# PowerV2.net
KiCad netlist of a schematic drawn in Altium Designer
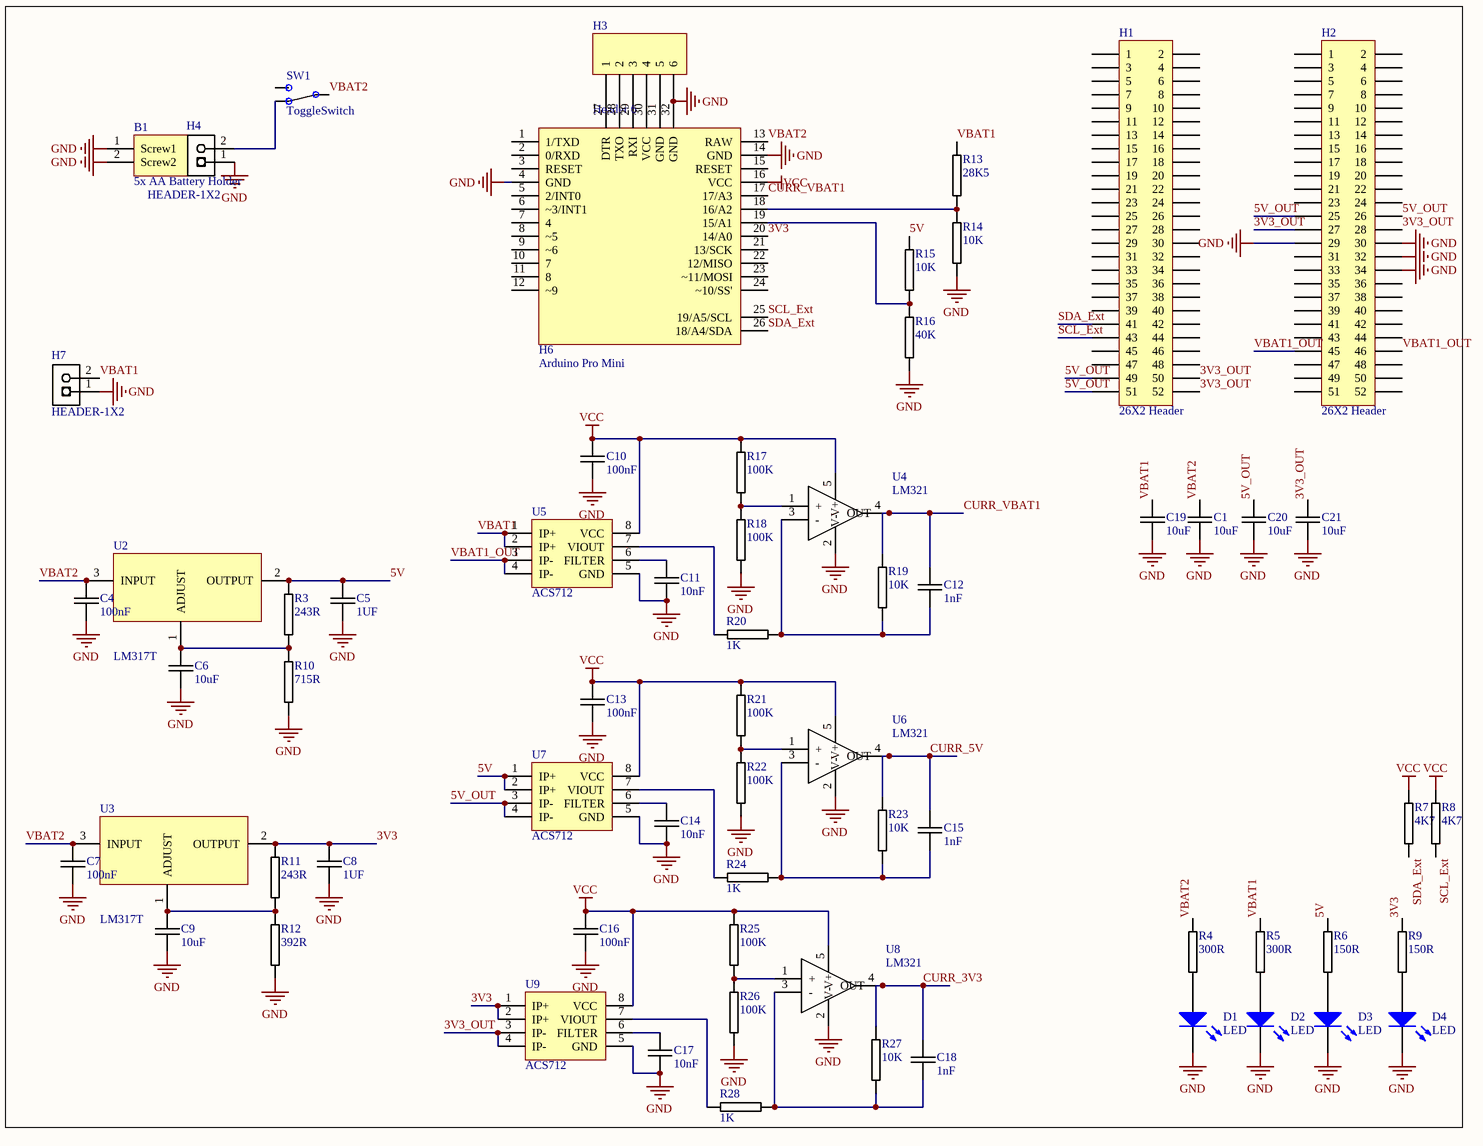
[diagram p0: PowerV2.SchDoc]

(export (version "E")
  (design (tool "Eeschema 10.0.6"))
  (components
    (comp (ref "B1")
      (value "5x AA Battery Holder")
      (footprint "5x AA Battery Holder")
      (libsource (lib "SupportComponents") (part "5x AA Battery Holder"))
    )
    (comp (ref "C1")
      (value "10uF")
      (footprint "0805C-GENERIC")
      (description "CAPACITOR 0805 CERAMIC")
      (fields
        (field (name "MANUFACTURER PART NUMBER") "C2012X5R1C106M")
        (field (name "MANUFACTURER") "TDK Corporation")
      )
      (libsource (lib "vh_altium_library") (part "0805C-10UF-16V-X5R-TDK"))
    )
    (comp (ref "C4")
      (value "100nF")
      (footprint "0805C-TBD")
      (description "CAPACITOR 0805 CERAMIC")
      (libsource (lib "vh_altium_library") (part "0805C-100nF-25V-X7R-MUR"))
    )
    (comp (ref "C5")
      (value "1UF")
      (footprint "0805C-GENERIC")
      (description "CAPACITOR 0805 CERAMIC")
      (fields
        (field (name "MANUFACTURER PART NUMBER") "ECJ-1VB0J225K")
        (field (name "MANUFACTURER") "Panasonic - ECG")
      )
      (libsource (lib "vh_altium_library") (part "0805C-2U2-6V3-X5R-PAN"))
    )
    (comp (ref "C6")
      (value "10uF")
      (footprint "0805C-GENERIC")
      (description "CAPACITOR 0805 CERAMIC")
      (libsource (lib "vh_altium_library") (part "0805C-10UF-25V-X5R-SAM"))
    )
    (comp (ref "C7")
      (value "100nF")
      (footprint "0805C-TBD")
      (description "CAPACITOR 0805 CERAMIC")
      (libsource (lib "vh_altium_library") (part "0805C-100nF-25V-X7R-MUR"))
    )
    (comp (ref "C8")
      (value "1UF")
      (footprint "0805C-GENERIC")
      (description "CAPACITOR 0805 CERAMIC")
      (fields
        (field (name "MANUFACTURER PART NUMBER") "ECJ-1VB0J225K")
        (field (name "MANUFACTURER") "Panasonic - ECG")
      )
      (libsource (lib "vh_altium_library") (part "0805C-2U2-6V3-X5R-PAN"))
    )
    (comp (ref "C9")
      (value "10uF")
      (footprint "0805C-GENERIC")
      (description "CAPACITOR 0805 CERAMIC")
      (libsource (lib "vh_altium_library") (part "0805C-10UF-25V-X5R-SAM"))
    )
    (comp (ref "C10")
      (value "100nF")
      (footprint "0805C-TBD")
      (description "CAPACITOR 0805 CERAMIC")
      (libsource (lib "vh_altium_library") (part "0805C-100nF-25V-X7R-MUR"))
    )
    (comp (ref "C11")
      (value "10nF")
      (footprint "0805C-TBD")
      (description "CAPACITOR 0805 CERAMIC")
      (libsource (lib "vh_altium_library") (part "0805C-100nF-25V-X7R-MUR"))
    )
    (comp (ref "C12")
      (value "1nF")
      (footprint "0805C-TBD")
      (description "CAPACITOR 0805 CERAMIC")
      (libsource (lib "vh_altium_library") (part "0805C-100nF-25V-X7R-MUR"))
    )
    (comp (ref "C13")
      (value "100nF")
      (footprint "0805C-TBD")
      (description "CAPACITOR 0805 CERAMIC")
      (libsource (lib "vh_altium_library") (part "0805C-100nF-25V-X7R-MUR"))
    )
    (comp (ref "C14")
      (value "10nF")
      (footprint "0805C-TBD")
      (description "CAPACITOR 0805 CERAMIC")
      (libsource (lib "vh_altium_library") (part "0805C-100nF-25V-X7R-MUR"))
    )
    (comp (ref "C15")
      (value "1nF")
      (footprint "0805C-TBD")
      (description "CAPACITOR 0805 CERAMIC")
      (libsource (lib "vh_altium_library") (part "0805C-100nF-25V-X7R-MUR"))
    )
    (comp (ref "C16")
      (value "100nF")
      (footprint "0805C-TBD")
      (description "CAPACITOR 0805 CERAMIC")
      (libsource (lib "vh_altium_library") (part "0805C-100nF-25V-X7R-MUR"))
    )
    (comp (ref "C17")
      (value "10nF")
      (footprint "0805C-TBD")
      (description "CAPACITOR 0805 CERAMIC")
      (libsource (lib "vh_altium_library") (part "0805C-100nF-25V-X7R-MUR"))
    )
    (comp (ref "C18")
      (value "1nF")
      (footprint "0805C-TBD")
      (description "CAPACITOR 0805 CERAMIC")
      (libsource (lib "vh_altium_library") (part "0805C-100nF-25V-X7R-MUR"))
    )
    (comp (ref "C19")
      (value "10uF")
      (footprint "0805C-GENERIC")
      (description "CAPACITOR 0805 CERAMIC")
      (fields
        (field (name "MANUFACTURER PART NUMBER") "C2012X5R1C106M")
        (field (name "MANUFACTURER") "TDK Corporation")
      )
      (libsource (lib "vh_altium_library") (part "0805C-10UF-16V-X5R-TDK"))
    )
    (comp (ref "C20")
      (value "10uF")
      (footprint "0805C-GENERIC")
      (description "CAPACITOR 0805 CERAMIC")
      (fields
        (field (name "MANUFACTURER PART NUMBER") "C2012X5R1C106M")
        (field (name "MANUFACTURER") "TDK Corporation")
      )
      (libsource (lib "vh_altium_library") (part "0805C-10UF-16V-X5R-TDK"))
    )
    (comp (ref "C21")
      (value "10uF")
      (footprint "0805C-GENERIC")
      (description "CAPACITOR 0805 CERAMIC")
      (fields
        (field (name "MANUFACTURER PART NUMBER") "C2012X5R1C106M")
        (field (name "MANUFACTURER") "TDK Corporation")
      )
      (libsource (lib "vh_altium_library") (part "0805C-10UF-16V-X5R-TDK"))
    )
    (comp (ref "D1")
      (value "LED")
      (footprint "LED")
      (description "Small LED")
      (libsource (lib "SupportComponents") (part "LED"))
    )
    (comp (ref "D2")
      (value "LED")
      (footprint "LED")
      (description "Small LED")
      (libsource (lib "SupportComponents") (part "LED"))
    )
    (comp (ref "D3")
      (value "LED")
      (footprint "LED")
      (description "Small LED")
      (libsource (lib "SupportComponents") (part "LED"))
    )
    (comp (ref "D4")
      (value "LED")
      (footprint "LED")
      (description "Small LED")
      (libsource (lib "SupportComponents") (part "LED"))
    )
    (comp (ref "H1")
      (value "26X2 Header")
      (footprint "26X2 Header")
      (libsource (lib "CustomParts") (part "26X2 Header"))
    )
    (comp (ref "H2")
      (value "26X2 Header")
      (footprint "26X2 Header")
      (libsource (lib "CustomParts") (part "26X2 Header"))
    )
    (comp (ref "H3")
      (value "Header 6")
      (footprint "HDR1X6")
      (description "Header, 6-Pin")
      (fields (field (name "PUBLISHER") "Altium Limited"))
      (libsource (lib "Miscellaneous Connectors") (part "Header 6"))
    )
    (comp (ref "H4")
      (value "HEADER-1X2")
      (footprint "HEADER-1X2")
      (libsource (lib "vh_altium_library") (part "HEADER-1X2"))
    )
    (comp (ref "H6")
      (value "Arduino Pro Mini")
      (footprint "Arduino Pro Mini")
      (libsource (lib "SupportComponents") (part "Arduino Pro Mini"))
    )
    (comp (ref "H7")
      (value "HEADER-1X2")
      (footprint "HEADER-1X2")
      (libsource (lib "vh_altium_library") (part "HEADER-1X2"))
    )
    (comp (ref "R3")
      (value "243R")
      (footprint "0805R-GENERIC")
      (description "RESISTOR 0805 1/3 WATT")
      (libsource (lib "vh_altium_library") (part "0805R-1R"))
    )
    (comp (ref "R4")
      (value "300R")
      (footprint "0805R-150")
      (description "RESISTOR 0805 1/4 WATT THIN FILM")
      (libsource (lib "vh_altium_library") (part "0805R-150"))
    )
    (comp (ref "R5")
      (value "300R")
      (footprint "0805R-150")
      (description "RESISTOR 0805 1/4 WATT THIN FILM")
      (libsource (lib "vh_altium_library") (part "0805R-150"))
    )
    (comp (ref "R6")
      (value "150R")
      (footprint "0805R-150")
      (description "RESISTOR 0805 1/4 WATT THIN FILM")
      (libsource (lib "vh_altium_library") (part "0805R-150"))
    )
    (comp (ref "R7")
      (value "4K7")
      (footprint "0805R-4K7")
      (description "RESISTOR 0805 1/4 WATT THIN FILM")
      (libsource (lib "vh_altium_library") (part "0805R-4K7"))
    )
    (comp (ref "R8")
      (value "4K7")
      (footprint "0805R-4K7")
      (description "RESISTOR 0805 1/4 WATT THIN FILM")
      (libsource (lib "vh_altium_library") (part "0805R-4K7"))
    )
    (comp (ref "R9")
      (value "150R")
      (footprint "0805R-150")
      (description "RESISTOR 0805 1/4 WATT THIN FILM")
      (libsource (lib "vh_altium_library") (part "0805R-150"))
    )
    (comp (ref "R10")
      (value "715R")
      (footprint "0805R-GENERIC")
      (description "RESISTOR 0805 1/3 WATT")
      (libsource (lib "vh_altium_library") (part "0805R-1R"))
    )
    (comp (ref "R11")
      (value "243R")
      (footprint "0805R-GENERIC")
      (description "RESISTOR 0805 1/3 WATT")
      (libsource (lib "vh_altium_library") (part "0805R-1R"))
    )
    (comp (ref "R12")
      (value "392R")
      (footprint "0805R-GENERIC")
      (description "RESISTOR 0805 1/3 WATT")
      (libsource (lib "vh_altium_library") (part "0805R-1R"))
    )
    (comp (ref "R13")
      (value "28K5")
      (footprint "0805R-10K")
      (description "RESISTOR 0805 1/4 WATT THIN FILM")
      (libsource (lib "vh_altium_library") (part "0805R-10K"))
    )
    (comp (ref "R14")
      (value "10K")
      (footprint "0805R-10K")
      (description "RESISTOR 0805 1/4 WATT THIN FILM")
      (libsource (lib "vh_altium_library") (part "0805R-10K"))
    )
    (comp (ref "R15")
      (value "10K")
      (footprint "0805R-10K")
      (description "RESISTOR 0805 1/4 WATT THIN FILM")
      (libsource (lib "vh_altium_library") (part "0805R-10K"))
    )
    (comp (ref "R16")
      (value "40K")
      (footprint "0805R-10K")
      (description "RESISTOR 0805 1/4 WATT THIN FILM")
      (libsource (lib "vh_altium_library") (part "0805R-10K"))
    )
    (comp (ref "R17")
      (value "100K")
      (footprint "0805R-100K")
      (description "RESISTOR 0805 1/4 WATT THIN FILM")
      (libsource (lib "vh_altium_library") (part "0805R-100K"))
    )
    (comp (ref "R18")
      (value "100K")
      (footprint "0805R-100K")
      (description "RESISTOR 0805 1/4 WATT THIN FILM")
      (libsource (lib "vh_altium_library") (part "0805R-100K"))
    )
    (comp (ref "R19")
      (value "10K")
      (footprint "0805R-3K3")
      (description "RESISTOR 0805 1/4 WATT THIN FILM")
      (libsource (lib "vh_altium_library") (part "0805R-3K3"))
    )
    (comp (ref "R20")
      (value "1K")
      (footprint "0805R-1K")
      (description "RESISTOR 0805 1/4 WATT THIN FILM")
      (libsource (lib "vh_altium_library") (part "0805R-1K"))
    )
    (comp (ref "R21")
      (value "100K")
      (footprint "0805R-100K")
      (description "RESISTOR 0805 1/4 WATT THIN FILM")
      (libsource (lib "vh_altium_library") (part "0805R-100K"))
    )
    (comp (ref "R22")
      (value "100K")
      (footprint "0805R-100K")
      (description "RESISTOR 0805 1/4 WATT THIN FILM")
      (libsource (lib "vh_altium_library") (part "0805R-100K"))
    )
    (comp (ref "R23")
      (value "10K")
      (footprint "0805R-3K3")
      (description "RESISTOR 0805 1/4 WATT THIN FILM")
      (libsource (lib "vh_altium_library") (part "0805R-3K3"))
    )
    (comp (ref "R24")
      (value "1K")
      (footprint "0805R-1K")
      (description "RESISTOR 0805 1/4 WATT THIN FILM")
      (libsource (lib "vh_altium_library") (part "0805R-1K"))
    )
    (comp (ref "R25")
      (value "100K")
      (footprint "0805R-100K")
      (description "RESISTOR 0805 1/4 WATT THIN FILM")
      (libsource (lib "vh_altium_library") (part "0805R-100K"))
    )
    (comp (ref "R26")
      (value "100K")
      (footprint "0805R-100K")
      (description "RESISTOR 0805 1/4 WATT THIN FILM")
      (libsource (lib "vh_altium_library") (part "0805R-100K"))
    )
    (comp (ref "R27")
      (value "10K")
      (footprint "0805R-3K3")
      (description "RESISTOR 0805 1/4 WATT THIN FILM")
      (libsource (lib "vh_altium_library") (part "0805R-3K3"))
    )
    (comp (ref "R28")
      (value "1K")
      (footprint "0805R-1K")
      (description "RESISTOR 0805 1/4 WATT THIN FILM")
      (libsource (lib "vh_altium_library") (part "0805R-1K"))
    )
    (comp (ref "SW1")
      (value "ToggleSwitch")
      (footprint "SWITCHFOOTPRINT")
      (libsource (lib "SupportComponents") (part "ToggleSwitch"))
    )
    (comp (ref "U2")
      (value "LM317T")
      (footprint "LM317T")
      (description "Adjustable Voltage Regulator")
      (libsource (lib "SupportComponents") (part "LM317T"))
    )
    (comp (ref "U3")
      (value "LM317T")
      (footprint "LM317T")
      (description "Adjustable Voltage Regulator")
      (libsource (lib "SupportComponents") (part "LM317T"))
    )
    (comp (ref "U4")
      (value "LM321")
      (footprint "LM321")
      (description "Op-amp")
      (libsource (lib "SupportComponents") (part "LM321"))
    )
    (comp (ref "U5")
      (value "ACS712")
      (footprint "ACS712")
      (description "Current Sensor")
      (libsource (lib "SupportComponents") (part "ACS712"))
    )
    (comp (ref "U6")
      (value "LM321")
      (footprint "LM321")
      (description "Op-amp")
      (libsource (lib "SupportComponents") (part "LM321"))
    )
    (comp (ref "U7")
      (value "ACS712")
      (footprint "ACS712")
      (description "Current Sensor")
      (libsource (lib "SupportComponents") (part "ACS712"))
    )
    (comp (ref "U8")
      (value "LM321")
      (footprint "LM321")
      (description "Op-amp")
      (libsource (lib "SupportComponents") (part "LM321"))
    )
    (comp (ref "U9")
      (value "ACS712")
      (footprint "ACS712")
      (description "Current Sensor")
      (libsource (lib "SupportComponents") (part "ACS712"))
    )
  )
  (nets
    (net (code "1") (name "/3V3") (class "Default")
      (node (ref "C8") (pin "1") (pintype "passive"))
      (node (ref "H6") (pin "20") (pinfunction "14/A0_20") (pintype "passive"))
      (node (ref "R11") (pin "2") (pintype "passive"))
      (node (ref "R9") (pin "1") (pintype "passive"))
      (node (ref "U3") (pin "2") (pinfunction "OUTPUT_2") (pintype "passive"))
      (node (ref "U9") (pin "1") (pinfunction "IP+_1") (pintype "passive"))
      (node (ref "U9") (pin "2") (pinfunction "IP+_2") (pintype "passive"))
    )
    (net (code "2") (name "/3V3_OUT") (class "Default")
      (node (ref "C21") (pin "1") (pintype "passive"))
      (node (ref "H1") (pin "50") (pinfunction "50_50") (pintype "passive"))
      (node (ref "H1") (pin "52") (pinfunction "52_52") (pintype "passive"))
      (node (ref "H2") (pin "27") (pinfunction "27_27") (pintype "passive"))
      (node (ref "H2") (pin "28") (pinfunction "28_28") (pintype "passive"))
      (node (ref "U9") (pin "3") (pinfunction "IP-_3") (pintype "passive"))
      (node (ref "U9") (pin "4") (pinfunction "IP-_4") (pintype "passive"))
    )
    (net (code "3") (name "/5V") (class "Default")
      (node (ref "C5") (pin "1") (pintype "passive"))
      (node (ref "R15") (pin "1") (pintype "passive"))
      (node (ref "R3") (pin "2") (pintype "passive"))
      (node (ref "R6") (pin "1") (pintype "passive"))
      (node (ref "U2") (pin "2") (pinfunction "OUTPUT_2") (pintype "passive"))
      (node (ref "U7") (pin "1") (pinfunction "IP+_1") (pintype "passive"))
      (node (ref "U7") (pin "2") (pinfunction "IP+_2") (pintype "passive"))
    )
    (net (code "4") (name "/5V_OUT") (class "Default")
      (node (ref "C20") (pin "1") (pintype "passive"))
      (node (ref "H1") (pin "49") (pinfunction "49_49") (pintype "passive"))
      (node (ref "H1") (pin "51") (pinfunction "51_51") (pintype "passive"))
      (node (ref "H2") (pin "25") (pinfunction "25_25") (pintype "passive"))
      (node (ref "H2") (pin "26") (pinfunction "26_26") (pintype "passive"))
      (node (ref "U7") (pin "3") (pinfunction "IP-_3") (pintype "passive"))
      (node (ref "U7") (pin "4") (pinfunction "IP-_4") (pintype "passive"))
    )
    (net (code "5") (name "/CURR_3V3") (class "Default")
      (node (ref "C18") (pin "1") (pintype "passive"))
      (node (ref "R27") (pin "1") (pintype "passive"))
      (node (ref "U8") (pin "4") (pinfunction "OUT_4") (pintype "passive"))
    )
    (net (code "6") (name "/CURR_5V") (class "Default")
      (node (ref "C15") (pin "1") (pintype "passive"))
      (node (ref "R23") (pin "1") (pintype "passive"))
      (node (ref "U6") (pin "4") (pinfunction "OUT_4") (pintype "passive"))
    )
    (net (code "7") (name "/CURR_VBAT1") (class "Default")
      (node (ref "C12") (pin "1") (pintype "passive"))
      (node (ref "H6") (pin "17") (pinfunction "17/A3_17") (pintype "passive"))
      (node (ref "R19") (pin "1") (pintype "passive"))
      (node (ref "U4") (pin "4") (pinfunction "OUT_4") (pintype "passive"))
    )
    (net (code "8") (name "/SCL_Ext") (class "Default")
      (node (ref "H1") (pin "43") (pinfunction "43_43") (pintype "passive"))
      (node (ref "H6") (pin "25") (pinfunction "19/A5/SCL_25") (pintype "passive"))
      (node (ref "R8") (pin "2") (pintype "passive"))
    )
    (net (code "9") (name "/SDA_Ext") (class "Default")
      (node (ref "H1") (pin "41") (pinfunction "41_41") (pintype "passive"))
      (node (ref "H6") (pin "26") (pinfunction "18/A4/SDA_26") (pintype "passive"))
      (node (ref "R7") (pin "2") (pintype "passive"))
    )
    (net (code "10") (name "/VBAT1") (class "Default")
      (node (ref "C19") (pin "1") (pintype "passive"))
      (node (ref "H7") (pin "2") (pintype "passive"))
      (node (ref "R13") (pin "1") (pintype "passive"))
      (node (ref "R5") (pin "1") (pintype "passive"))
      (node (ref "U5") (pin "1") (pinfunction "IP+_1") (pintype "passive"))
      (node (ref "U5") (pin "2") (pinfunction "IP+_2") (pintype "passive"))
    )
    (net (code "11") (name "/VBAT1_OUT") (class "Default")
      (node (ref "H2") (pin "45") (pinfunction "45_45") (pintype "passive"))
      (node (ref "H2") (pin "46") (pinfunction "46_46") (pintype "passive"))
      (node (ref "U5") (pin "3") (pinfunction "IP-_3") (pintype "passive"))
      (node (ref "U5") (pin "4") (pinfunction "IP-_4") (pintype "passive"))
    )
    (net (code "12") (name "/VBAT2") (class "Default")
      (node (ref "C1") (pin "1") (pintype "passive"))
      (node (ref "C4") (pin "1") (pintype "passive"))
      (node (ref "C7") (pin "1") (pintype "passive"))
      (node (ref "H6") (pin "13") (pinfunction "RAW_13") (pintype "passive"))
      (node (ref "R4") (pin "1") (pintype "passive"))
      (node (ref "SW1") (pin "23") (pinfunction "23_23") (pintype "passive"))
      (node (ref "U2") (pin "3") (pinfunction "INPUT_3") (pintype "passive"))
      (node (ref "U3") (pin "3") (pinfunction "INPUT_3") (pintype "passive"))
    )
    (net (code "13") (name "GND") (class "Default")
      (node (ref "B1") (pin "1") (pinfunction "Screw1_1") (pintype "passive"))
      (node (ref "B1") (pin "2") (pinfunction "Screw2_2") (pintype "passive"))
      (node (ref "C1") (pin "2") (pintype "passive"))
      (node (ref "C10") (pin "2") (pintype "passive"))
      (node (ref "C11") (pin "2") (pintype "passive"))
      (node (ref "C13") (pin "2") (pintype "passive"))
      (node (ref "C14") (pin "2") (pintype "passive"))
      (node (ref "C16") (pin "2") (pintype "passive"))
      (node (ref "C17") (pin "2") (pintype "passive"))
      (node (ref "C19") (pin "2") (pintype "passive"))
      (node (ref "C20") (pin "2") (pintype "passive"))
      (node (ref "C21") (pin "2") (pintype "passive"))
      (node (ref "C4") (pin "2") (pintype "passive"))
      (node (ref "C5") (pin "2") (pintype "passive"))
      (node (ref "C6") (pin "2") (pintype "passive"))
      (node (ref "C7") (pin "2") (pintype "passive"))
      (node (ref "C8") (pin "2") (pintype "passive"))
      (node (ref "C9") (pin "2") (pintype "passive"))
      (node (ref "D1") (pin "2") (pinfunction "K_2") (pintype "passive"))
      (node (ref "D2") (pin "2") (pinfunction "K_2") (pintype "passive"))
      (node (ref "D3") (pin "2") (pinfunction "K_2") (pintype "passive"))
      (node (ref "D4") (pin "2") (pinfunction "K_2") (pintype "passive"))
      (node (ref "H2") (pin "29") (pinfunction "29_29") (pintype "passive"))
      (node (ref "H2") (pin "30") (pinfunction "30_30") (pintype "passive"))
      (node (ref "H2") (pin "32") (pinfunction "32_32") (pintype "passive"))
      (node (ref "H2") (pin "34") (pinfunction "34_34") (pintype "passive"))
      (node (ref "H3") (pin "6") (pinfunction "6_6") (pintype "passive"))
      (node (ref "H4") (pin "1") (pintype "passive"))
      (node (ref "H6") (pin "14") (pinfunction "GND_14") (pintype "passive"))
      (node (ref "H6") (pin "32") (pinfunction "GND_32") (pintype "passive"))
      (node (ref "H6") (pin "4") (pinfunction "GND_4") (pintype "passive"))
      (node (ref "H7") (pin "1") (pintype "passive"))
      (node (ref "R10") (pin "2") (pintype "passive"))
      (node (ref "R12") (pin "2") (pintype "passive"))
      (node (ref "R14") (pin "2") (pintype "passive"))
      (node (ref "R16") (pin "2") (pintype "passive"))
      (node (ref "R18") (pin "2") (pintype "passive"))
      (node (ref "R22") (pin "2") (pintype "passive"))
      (node (ref "R26") (pin "2") (pintype "passive"))
      (node (ref "U4") (pin "2") (pinfunction "V-_2") (pintype "passive"))
      (node (ref "U5") (pin "5") (pinfunction "GND_5") (pintype "passive"))
      (node (ref "U6") (pin "2") (pinfunction "V-_2") (pintype "passive"))
      (node (ref "U7") (pin "5") (pinfunction "GND_5") (pintype "passive"))
      (node (ref "U8") (pin "2") (pinfunction "V-_2") (pintype "passive"))
      (node (ref "U9") (pin "5") (pinfunction "GND_5") (pintype "passive"))
    )
    (net (code "14") (name "Net-(D1-A)") (class "Default")
      (node (ref "D1") (pin "1") (pinfunction "A_1") (pintype "passive"))
      (node (ref "R4") (pin "2") (pintype "passive"))
    )
    (net (code "15") (name "Net-(D2-A)") (class "Default")
      (node (ref "D2") (pin "1") (pinfunction "A_1") (pintype "passive"))
      (node (ref "R5") (pin "2") (pintype "passive"))
    )
    (net (code "16") (name "Net-(D3-A)") (class "Default")
      (node (ref "D3") (pin "1") (pinfunction "A_1") (pintype "passive"))
      (node (ref "R6") (pin "2") (pintype "passive"))
    )
    (net (code "17") (name "Net-(D4-A)") (class "Default")
      (node (ref "D4") (pin "1") (pinfunction "A_1") (pintype "passive"))
      (node (ref "R9") (pin "2") (pintype "passive"))
    )
    (net (code "18") (name "Net-(H3-Pad4)") (class "Default")
      (node (ref "H3") (pin "4") (pinfunction "4_4") (pintype "passive"))
      (node (ref "H6") (pin "30") (pinfunction "VCC_30") (pintype "passive"))
    )
    (net (code "19") (name "Net-(H3-Pad5)") (class "Default")
      (node (ref "H3") (pin "5") (pinfunction "5_5") (pintype "passive"))
      (node (ref "H6") (pin "31") (pinfunction "GND_31") (pintype "passive"))
    )
    (net (code "20") (name "Net-(H4-Pad2)") (class "Default")
      (node (ref "H4") (pin "2") (pintype "passive"))
      (node (ref "SW1") (pin "24") (pinfunction "24_24") (pintype "passive"))
    )
    (net (code "21") (name "Net-(H6-15{slash}A1)") (class "Default")
      (node (ref "H6") (pin "19") (pinfunction "15/A1_19") (pintype "passive"))
      (node (ref "R15") (pin "2") (pintype "passive"))
      (node (ref "R16") (pin "1") (pintype "passive"))
    )
    (net (code "22") (name "Net-(H6-16{slash}A2)") (class "Default")
      (node (ref "H6") (pin "18") (pinfunction "16/A2_18") (pintype "passive"))
      (node (ref "R13") (pin "2") (pintype "passive"))
      (node (ref "R14") (pin "1") (pintype "passive"))
    )
    (net (code "23") (name "Net-(H6-DTR)") (class "Default")
      (node (ref "H3") (pin "1") (pinfunction "1_1") (pintype "passive"))
      (node (ref "H6") (pin "27") (pinfunction "DTR_27") (pintype "passive"))
    )
    (net (code "24") (name "Net-(H6-RXI)") (class "Default")
      (node (ref "H3") (pin "3") (pinfunction "3_3") (pintype "passive"))
      (node (ref "H6") (pin "29") (pinfunction "RXI_29") (pintype "passive"))
    )
    (net (code "25") (name "Net-(H6-TXO)") (class "Default")
      (node (ref "H3") (pin "2") (pinfunction "2_2") (pintype "passive"))
      (node (ref "H6") (pin "28") (pinfunction "TXO_28") (pintype "passive"))
    )
    (net (code "26") (name "Net-(U2-ADJUST)") (class "Default")
      (node (ref "C6") (pin "1") (pintype "passive"))
      (node (ref "R10") (pin "1") (pintype "passive"))
      (node (ref "R3") (pin "1") (pintype "passive"))
      (node (ref "U2") (pin "1") (pinfunction "ADJUST_1") (pintype "passive"))
    )
    (net (code "27") (name "Net-(U3-ADJUST)") (class "Default")
      (node (ref "C9") (pin "1") (pintype "passive"))
      (node (ref "R11") (pin "1") (pintype "passive"))
      (node (ref "R12") (pin "1") (pintype "passive"))
      (node (ref "U3") (pin "1") (pinfunction "ADJUST_1") (pintype "passive"))
    )
    (net (code "28") (name "Net-(U4-+)") (class "Default")
      (node (ref "R17") (pin "2") (pintype "passive"))
      (node (ref "R18") (pin "1") (pintype "passive"))
      (node (ref "U4") (pin "1") (pinfunction "+_1") (pintype "passive"))
    )
    (net (code "29") (name "Net-(U4--)") (class "Default")
      (node (ref "C12") (pin "2") (pintype "passive"))
      (node (ref "R19") (pin "2") (pintype "passive"))
      (node (ref "R20") (pin "2") (pintype "passive"))
      (node (ref "U4") (pin "3") (pinfunction "-_3") (pintype "passive"))
    )
    (net (code "30") (name "Net-(U5-FILTER)") (class "Default")
      (node (ref "C11") (pin "1") (pintype "passive"))
      (node (ref "U5") (pin "6") (pinfunction "FILTER_6") (pintype "passive"))
    )
    (net (code "31") (name "Net-(U5-VIOUT)") (class "Default")
      (node (ref "R20") (pin "1") (pintype "passive"))
      (node (ref "U5") (pin "7") (pinfunction "VIOUT_7") (pintype "passive"))
    )
    (net (code "32") (name "Net-(U6-+)") (class "Default")
      (node (ref "R21") (pin "2") (pintype "passive"))
      (node (ref "R22") (pin "1") (pintype "passive"))
      (node (ref "U6") (pin "1") (pinfunction "+_1") (pintype "passive"))
    )
    (net (code "33") (name "Net-(U6--)") (class "Default")
      (node (ref "C15") (pin "2") (pintype "passive"))
      (node (ref "R23") (pin "2") (pintype "passive"))
      (node (ref "R24") (pin "2") (pintype "passive"))
      (node (ref "U6") (pin "3") (pinfunction "-_3") (pintype "passive"))
    )
    (net (code "34") (name "Net-(U7-FILTER)") (class "Default")
      (node (ref "C14") (pin "1") (pintype "passive"))
      (node (ref "U7") (pin "6") (pinfunction "FILTER_6") (pintype "passive"))
    )
    (net (code "35") (name "Net-(U7-VIOUT)") (class "Default")
      (node (ref "R24") (pin "1") (pintype "passive"))
      (node (ref "U7") (pin "7") (pinfunction "VIOUT_7") (pintype "passive"))
    )
    (net (code "36") (name "Net-(U8-+)") (class "Default")
      (node (ref "R25") (pin "2") (pintype "passive"))
      (node (ref "R26") (pin "1") (pintype "passive"))
      (node (ref "U8") (pin "1") (pinfunction "+_1") (pintype "passive"))
    )
    (net (code "37") (name "Net-(U8--)") (class "Default")
      (node (ref "C18") (pin "2") (pintype "passive"))
      (node (ref "R27") (pin "2") (pintype "passive"))
      (node (ref "R28") (pin "2") (pintype "passive"))
      (node (ref "U8") (pin "3") (pinfunction "-_3") (pintype "passive"))
    )
    (net (code "38") (name "Net-(U9-FILTER)") (class "Default")
      (node (ref "C17") (pin "1") (pintype "passive"))
      (node (ref "U9") (pin "6") (pinfunction "FILTER_6") (pintype "passive"))
    )
    (net (code "39") (name "Net-(U9-VIOUT)") (class "Default")
      (node (ref "R28") (pin "1") (pintype "passive"))
      (node (ref "U9") (pin "7") (pinfunction "VIOUT_7") (pintype "passive"))
    )
    (net (code "40") (name "VCC") (class "Default")
      (node (ref "C10") (pin "1") (pintype "passive"))
      (node (ref "C13") (pin "1") (pintype "passive"))
      (node (ref "C16") (pin "1") (pintype "passive"))
      (node (ref "H6") (pin "16") (pinfunction "VCC_16") (pintype "passive"))
      (node (ref "R17") (pin "1") (pintype "passive"))
      (node (ref "R21") (pin "1") (pintype "passive"))
      (node (ref "R25") (pin "1") (pintype "passive"))
      (node (ref "R7") (pin "1") (pintype "passive"))
      (node (ref "R8") (pin "1") (pintype "passive"))
      (node (ref "U4") (pin "5") (pinfunction "V+_5") (pintype "passive"))
      (node (ref "U5") (pin "8") (pinfunction "VCC_8") (pintype "passive"))
      (node (ref "U6") (pin "5") (pinfunction "V+_5") (pintype "passive"))
      (node (ref "U7") (pin "8") (pinfunction "VCC_8") (pintype "passive"))
      (node (ref "U8") (pin "5") (pinfunction "V+_5") (pintype "passive"))
      (node (ref "U9") (pin "8") (pinfunction "VCC_8") (pintype "passive"))
    )
    (net (code "41") (name "unconnected-(H1-Pad1)") (class "Default")
      (node (ref "H1") (pin "1") (pinfunction "1_1") (pintype "passive"))
    )
    (net (code "42") (name "unconnected-(H1-Pad2)") (class "Default")
      (node (ref "H1") (pin "2") (pinfunction "2_2") (pintype "passive"))
    )
    (net (code "43") (name "unconnected-(H1-Pad3)") (class "Default")
      (node (ref "H1") (pin "3") (pinfunction "3_3") (pintype "passive"))
    )
    (net (code "44") (name "unconnected-(H1-Pad4)") (class "Default")
      (node (ref "H1") (pin "4") (pinfunction "4_4") (pintype "passive"))
    )
    (net (code "45") (name "unconnected-(H1-Pad5)") (class "Default")
      (node (ref "H1") (pin "5") (pinfunction "5_5") (pintype "passive"))
    )
    (net (code "46") (name "unconnected-(H1-Pad6)") (class "Default")
      (node (ref "H1") (pin "6") (pinfunction "6_6") (pintype "passive"))
    )
    (net (code "47") (name "unconnected-(H1-Pad7)") (class "Default")
      (node (ref "H1") (pin "7") (pinfunction "7_7") (pintype "passive"))
    )
    (net (code "48") (name "unconnected-(H1-Pad8)") (class "Default")
      (node (ref "H1") (pin "8") (pinfunction "8_8") (pintype "passive"))
    )
    (net (code "49") (name "unconnected-(H1-Pad9)") (class "Default")
      (node (ref "H1") (pin "9") (pinfunction "9_9") (pintype "passive"))
    )
    (net (code "50") (name "unconnected-(H1-Pad10)") (class "Default")
      (node (ref "H1") (pin "10") (pinfunction "10_10") (pintype "passive"))
    )
    (net (code "51") (name "unconnected-(H1-Pad11)") (class "Default")
      (node (ref "H1") (pin "11") (pinfunction "11_11") (pintype "passive"))
    )
    (net (code "52") (name "unconnected-(H1-Pad12)") (class "Default")
      (node (ref "H1") (pin "12") (pinfunction "12_12") (pintype "passive"))
    )
    (net (code "53") (name "unconnected-(H1-Pad13)") (class "Default")
      (node (ref "H1") (pin "13") (pinfunction "13_13") (pintype "passive"))
    )
    (net (code "54") (name "unconnected-(H1-Pad14)") (class "Default")
      (node (ref "H1") (pin "14") (pinfunction "14_14") (pintype "passive"))
    )
    (net (code "55") (name "unconnected-(H1-Pad15)") (class "Default")
      (node (ref "H1") (pin "15") (pinfunction "15_15") (pintype "passive"))
    )
    (net (code "56") (name "unconnected-(H1-Pad16)") (class "Default")
      (node (ref "H1") (pin "16") (pinfunction "16_16") (pintype "passive"))
    )
    (net (code "57") (name "unconnected-(H1-Pad17)") (class "Default")
      (node (ref "H1") (pin "17") (pinfunction "17_17") (pintype "passive"))
    )
    (net (code "58") (name "unconnected-(H1-Pad18)") (class "Default")
      (node (ref "H1") (pin "18") (pinfunction "18_18") (pintype "passive"))
    )
    (net (code "59") (name "unconnected-(H1-Pad19)") (class "Default")
      (node (ref "H1") (pin "19") (pinfunction "19_19") (pintype "passive"))
    )
    (net (code "60") (name "unconnected-(H1-Pad20)") (class "Default")
      (node (ref "H1") (pin "20") (pinfunction "20_20") (pintype "passive"))
    )
    (net (code "61") (name "unconnected-(H1-Pad21)") (class "Default")
      (node (ref "H1") (pin "21") (pinfunction "21_21") (pintype "passive"))
    )
    (net (code "62") (name "unconnected-(H1-Pad22)") (class "Default")
      (node (ref "H1") (pin "22") (pinfunction "22_22") (pintype "passive"))
    )
    (net (code "63") (name "unconnected-(H1-Pad23)") (class "Default")
      (node (ref "H1") (pin "23") (pinfunction "23_23") (pintype "passive"))
    )
    (net (code "64") (name "unconnected-(H1-Pad24)") (class "Default")
      (node (ref "H1") (pin "24") (pinfunction "24_24") (pintype "passive"))
    )
    (net (code "65") (name "unconnected-(H1-Pad25)") (class "Default")
      (node (ref "H1") (pin "25") (pinfunction "25_25") (pintype "passive"))
    )
    (net (code "66") (name "unconnected-(H1-Pad26)") (class "Default")
      (node (ref "H1") (pin "26") (pinfunction "26_26") (pintype "passive"))
    )
    (net (code "67") (name "unconnected-(H1-Pad27)") (class "Default")
      (node (ref "H1") (pin "27") (pinfunction "27_27") (pintype "passive"))
    )
    (net (code "68") (name "unconnected-(H1-Pad28)") (class "Default")
      (node (ref "H1") (pin "28") (pinfunction "28_28") (pintype "passive"))
    )
    (net (code "69") (name "unconnected-(H1-Pad29)") (class "Default")
      (node (ref "H1") (pin "29") (pinfunction "29_29") (pintype "passive"))
    )
    (net (code "70") (name "unconnected-(H1-Pad30)") (class "Default")
      (node (ref "H1") (pin "30") (pinfunction "30_30") (pintype "passive"))
    )
    (net (code "71") (name "unconnected-(H1-Pad31)") (class "Default")
      (node (ref "H1") (pin "31") (pinfunction "31_31") (pintype "passive"))
    )
    (net (code "72") (name "unconnected-(H1-Pad32)") (class "Default")
      (node (ref "H1") (pin "32") (pinfunction "32_32") (pintype "passive"))
    )
    (net (code "73") (name "unconnected-(H1-Pad33)") (class "Default")
      (node (ref "H1") (pin "33") (pinfunction "33_33") (pintype "passive"))
    )
    (net (code "74") (name "unconnected-(H1-Pad34)") (class "Default")
      (node (ref "H1") (pin "34") (pinfunction "34_34") (pintype "passive"))
    )
    (net (code "75") (name "unconnected-(H1-Pad35)") (class "Default")
      (node (ref "H1") (pin "35") (pinfunction "35_35") (pintype "passive"))
    )
    (net (code "76") (name "unconnected-(H1-Pad36)") (class "Default")
      (node (ref "H1") (pin "36") (pinfunction "36_36") (pintype "passive"))
    )
    (net (code "77") (name "unconnected-(H1-Pad37)") (class "Default")
      (node (ref "H1") (pin "37") (pinfunction "37_37") (pintype "passive"))
    )
    (net (code "78") (name "unconnected-(H1-Pad38)") (class "Default")
      (node (ref "H1") (pin "38") (pinfunction "38_38") (pintype "passive"))
    )
    (net (code "79") (name "unconnected-(H1-Pad39)") (class "Default")
      (node (ref "H1") (pin "39") (pinfunction "39_39") (pintype "passive"))
    )
    (net (code "80") (name "unconnected-(H1-Pad40)") (class "Default")
      (node (ref "H1") (pin "40") (pinfunction "40_40") (pintype "passive"))
    )
    (net (code "81") (name "unconnected-(H1-Pad42)") (class "Default")
      (node (ref "H1") (pin "42") (pinfunction "42_42") (pintype "passive"))
    )
    (net (code "82") (name "unconnected-(H1-Pad44)") (class "Default")
      (node (ref "H1") (pin "44") (pinfunction "44_44") (pintype "passive"))
    )
    (net (code "83") (name "unconnected-(H1-Pad45)") (class "Default")
      (node (ref "H1") (pin "45") (pinfunction "45_45") (pintype "passive"))
    )
    (net (code "84") (name "unconnected-(H1-Pad46)") (class "Default")
      (node (ref "H1") (pin "46") (pinfunction "46_46") (pintype "passive"))
    )
    (net (code "85") (name "unconnected-(H1-Pad47)") (class "Default")
      (node (ref "H1") (pin "47") (pinfunction "47_47") (pintype "passive"))
    )
    (net (code "86") (name "unconnected-(H1-Pad48)") (class "Default")
      (node (ref "H1") (pin "48") (pinfunction "48_48") (pintype "passive"))
    )
    (net (code "87") (name "unconnected-(H2-Pad1)") (class "Default")
      (node (ref "H2") (pin "1") (pinfunction "1_1") (pintype "passive"))
    )
    (net (code "88") (name "unconnected-(H2-Pad2)") (class "Default")
      (node (ref "H2") (pin "2") (pinfunction "2_2") (pintype "passive"))
    )
    (net (code "89") (name "unconnected-(H2-Pad3)") (class "Default")
      (node (ref "H2") (pin "3") (pinfunction "3_3") (pintype "passive"))
    )
    (net (code "90") (name "unconnected-(H2-Pad4)") (class "Default")
      (node (ref "H2") (pin "4") (pinfunction "4_4") (pintype "passive"))
    )
    (net (code "91") (name "unconnected-(H2-Pad5)") (class "Default")
      (node (ref "H2") (pin "5") (pinfunction "5_5") (pintype "passive"))
    )
    (net (code "92") (name "unconnected-(H2-Pad6)") (class "Default")
      (node (ref "H2") (pin "6") (pinfunction "6_6") (pintype "passive"))
    )
    (net (code "93") (name "unconnected-(H2-Pad7)") (class "Default")
      (node (ref "H2") (pin "7") (pinfunction "7_7") (pintype "passive"))
    )
    (net (code "94") (name "unconnected-(H2-Pad8)") (class "Default")
      (node (ref "H2") (pin "8") (pinfunction "8_8") (pintype "passive"))
    )
    (net (code "95") (name "unconnected-(H2-Pad9)") (class "Default")
      (node (ref "H2") (pin "9") (pinfunction "9_9") (pintype "passive"))
    )
    (net (code "96") (name "unconnected-(H2-Pad10)") (class "Default")
      (node (ref "H2") (pin "10") (pinfunction "10_10") (pintype "passive"))
    )
    (net (code "97") (name "unconnected-(H2-Pad11)") (class "Default")
      (node (ref "H2") (pin "11") (pinfunction "11_11") (pintype "passive"))
    )
    (net (code "98") (name "unconnected-(H2-Pad12)") (class "Default")
      (node (ref "H2") (pin "12") (pinfunction "12_12") (pintype "passive"))
    )
    (net (code "99") (name "unconnected-(H2-Pad13)") (class "Default")
      (node (ref "H2") (pin "13") (pinfunction "13_13") (pintype "passive"))
    )
    (net (code "100") (name "unconnected-(H2-Pad14)") (class "Default")
      (node (ref "H2") (pin "14") (pinfunction "14_14") (pintype "passive"))
    )
    (net (code "101") (name "unconnected-(H2-Pad15)") (class "Default")
      (node (ref "H2") (pin "15") (pinfunction "15_15") (pintype "passive"))
    )
    (net (code "102") (name "unconnected-(H2-Pad16)") (class "Default")
      (node (ref "H2") (pin "16") (pinfunction "16_16") (pintype "passive"))
    )
    (net (code "103") (name "unconnected-(H2-Pad17)") (class "Default")
      (node (ref "H2") (pin "17") (pinfunction "17_17") (pintype "passive"))
    )
    (net (code "104") (name "unconnected-(H2-Pad18)") (class "Default")
      (node (ref "H2") (pin "18") (pinfunction "18_18") (pintype "passive"))
    )
    (net (code "105") (name "unconnected-(H2-Pad19)") (class "Default")
      (node (ref "H2") (pin "19") (pinfunction "19_19") (pintype "passive"))
    )
    (net (code "106") (name "unconnected-(H2-Pad20)") (class "Default")
      (node (ref "H2") (pin "20") (pinfunction "20_20") (pintype "passive"))
    )
    (net (code "107") (name "unconnected-(H2-Pad21)") (class "Default")
      (node (ref "H2") (pin "21") (pinfunction "21_21") (pintype "passive"))
    )
    (net (code "108") (name "unconnected-(H2-Pad22)") (class "Default")
      (node (ref "H2") (pin "22") (pinfunction "22_22") (pintype "passive"))
    )
    (net (code "109") (name "unconnected-(H2-Pad23)") (class "Default")
      (node (ref "H2") (pin "23") (pinfunction "23_23") (pintype "passive"))
    )
    (net (code "110") (name "unconnected-(H2-Pad24)") (class "Default")
      (node (ref "H2") (pin "24") (pinfunction "24_24") (pintype "passive"))
    )
    (net (code "111") (name "unconnected-(H2-Pad31)") (class "Default")
      (node (ref "H2") (pin "31") (pinfunction "31_31") (pintype "passive"))
    )
    (net (code "112") (name "unconnected-(H2-Pad33)") (class "Default")
      (node (ref "H2") (pin "33") (pinfunction "33_33") (pintype "passive"))
    )
    (net (code "113") (name "unconnected-(H2-Pad35)") (class "Default")
      (node (ref "H2") (pin "35") (pinfunction "35_35") (pintype "passive"))
    )
    (net (code "114") (name "unconnected-(H2-Pad36)") (class "Default")
      (node (ref "H2") (pin "36") (pinfunction "36_36") (pintype "passive"))
    )
    (net (code "115") (name "unconnected-(H2-Pad37)") (class "Default")
      (node (ref "H2") (pin "37") (pinfunction "37_37") (pintype "passive"))
    )
    (net (code "116") (name "unconnected-(H2-Pad38)") (class "Default")
      (node (ref "H2") (pin "38") (pinfunction "38_38") (pintype "passive"))
    )
    (net (code "117") (name "unconnected-(H2-Pad39)") (class "Default")
      (node (ref "H2") (pin "39") (pinfunction "39_39") (pintype "passive"))
    )
    (net (code "118") (name "unconnected-(H2-Pad40)") (class "Default")
      (node (ref "H2") (pin "40") (pinfunction "40_40") (pintype "passive"))
    )
    (net (code "119") (name "unconnected-(H2-Pad41)") (class "Default")
      (node (ref "H2") (pin "41") (pinfunction "41_41") (pintype "passive"))
    )
    (net (code "120") (name "unconnected-(H2-Pad42)") (class "Default")
      (node (ref "H2") (pin "42") (pinfunction "42_42") (pintype "passive"))
    )
    (net (code "121") (name "unconnected-(H2-Pad43)") (class "Default")
      (node (ref "H2") (pin "43") (pinfunction "43_43") (pintype "passive"))
    )
    (net (code "122") (name "unconnected-(H2-Pad44)") (class "Default")
      (node (ref "H2") (pin "44") (pinfunction "44_44") (pintype "passive"))
    )
    (net (code "123") (name "unconnected-(H2-Pad47)") (class "Default")
      (node (ref "H2") (pin "47") (pinfunction "47_47") (pintype "passive"))
    )
    (net (code "124") (name "unconnected-(H2-Pad48)") (class "Default")
      (node (ref "H2") (pin "48") (pinfunction "48_48") (pintype "passive"))
    )
    (net (code "125") (name "unconnected-(H2-Pad49)") (class "Default")
      (node (ref "H2") (pin "49") (pinfunction "49_49") (pintype "passive"))
    )
    (net (code "126") (name "unconnected-(H2-Pad50)") (class "Default")
      (node (ref "H2") (pin "50") (pinfunction "50_50") (pintype "passive"))
    )
    (net (code "127") (name "unconnected-(H2-Pad51)") (class "Default")
      (node (ref "H2") (pin "51") (pinfunction "51_51") (pintype "passive"))
    )
    (net (code "128") (name "unconnected-(H2-Pad52)") (class "Default")
      (node (ref "H2") (pin "52") (pinfunction "52_52") (pintype "passive"))
    )
    (net (code "129") (name "unconnected-(H6-0{slash}RXD-Pad2)") (class "Default")
      (node (ref "H6") (pin "2") (pinfunction "0/RXD_2") (pintype "passive"))
    )
    (net (code "130") (name "unconnected-(H6-1{slash}TXD-Pad1)") (class "Default")
      (node (ref "H6") (pin "1") (pinfunction "1/TXD_1") (pintype "passive"))
    )
    (net (code "131") (name "unconnected-(H6-2{slash}INT0-Pad5)") (class "Default")
      (node (ref "H6") (pin "5") (pinfunction "2/INT0_5") (pintype "passive"))
    )
    (net (code "132") (name "unconnected-(H6-4-Pad7)") (class "Default")
      (node (ref "H6") (pin "7") (pinfunction "4_7") (pintype "passive"))
    )
    (net (code "133") (name "unconnected-(H6-7-Pad10)") (class "Default")
      (node (ref "H6") (pin "10") (pinfunction "7_10") (pintype "passive"))
    )
    (net (code "134") (name "unconnected-(H6-8-Pad11)") (class "Default")
      (node (ref "H6") (pin "11") (pinfunction "8_11") (pintype "passive"))
    )
    (net (code "135") (name "unconnected-(H6-12{slash}MISO-Pad22)") (class "Default")
      (node (ref "H6") (pin "22") (pinfunction "12/MISO_22") (pintype "passive"))
    )
    (net (code "136") (name "unconnected-(H6-13{slash}SCK-Pad21)") (class "Default")
      (node (ref "H6") (pin "21") (pinfunction "13/SCK_21") (pintype "passive"))
    )
    (net (code "137") (name "unconnected-(H6-RESET-Pad3)") (class "Default")
      (node (ref "H6") (pin "3") (pinfunction "RESET_3") (pintype "passive"))
    )
    (net (code "138") (name "unconnected-(H6-RESET-Pad15)") (class "Default")
      (node (ref "H6") (pin "15") (pinfunction "RESET_15") (pintype "passive"))
    )
    (net (code "139") (name "unconnected-(H6-~3{slash}INT1-Pad6)") (class "Default")
      (node (ref "H6") (pin "6") (pinfunction "~3/INT1_6") (pintype "passive"))
    )
    (net (code "140") (name "unconnected-(H6-~5-Pad8)") (class "Default")
      (node (ref "H6") (pin "8") (pinfunction "~5_8") (pintype "passive"))
    )
    (net (code "141") (name "unconnected-(H6-~6-Pad9)") (class "Default")
      (node (ref "H6") (pin "9") (pinfunction "~6_9") (pintype "passive"))
    )
    (net (code "142") (name "unconnected-(H6-~9-Pad12)") (class "Default")
      (node (ref "H6") (pin "12") (pinfunction "~9_12") (pintype "passive"))
    )
    (net (code "143") (name "unconnected-(H6-~10{slash}SS'-Pad24)") (class "Default")
      (node (ref "H6") (pin "24") (pinfunction "~10/SS'_24") (pintype "passive"))
    )
    (net (code "144") (name "unconnected-(H6-~11{slash}MOSI-Pad23)") (class "Default")
      (node (ref "H6") (pin "23") (pinfunction "~11/MOSI_23") (pintype "passive"))
    )
    (net (code "145") (name "unconnected-(SW1-Pad25)") (class "Default")
      (node (ref "SW1") (pin "25") (pinfunction "25_25") (pintype "passive"))
    )
  )
)
